# core.net
KiCad netlist of a schematic drawn in EAGLE
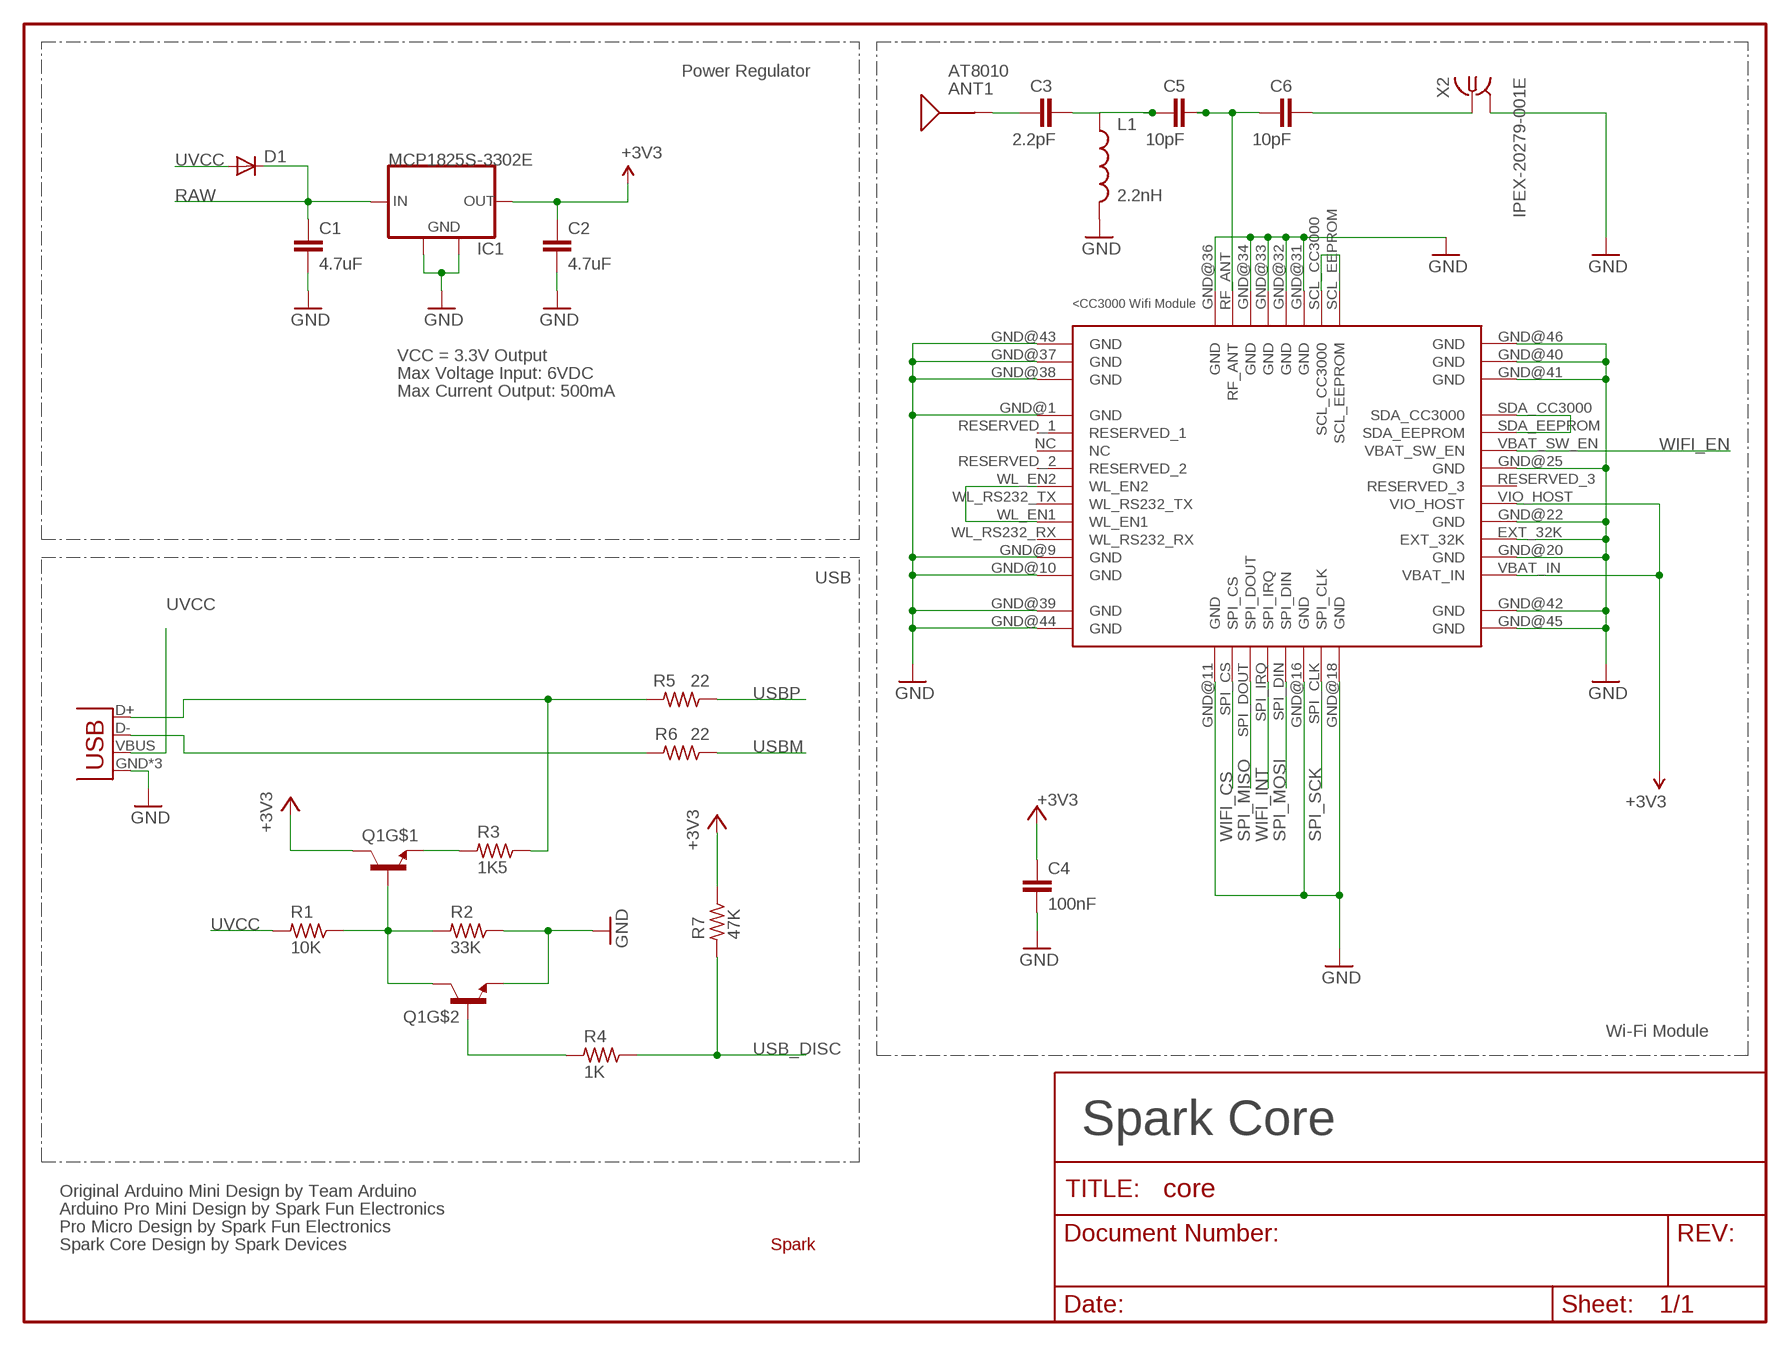
[diagram p0: schematic, sheet 1, part 1 of 2]
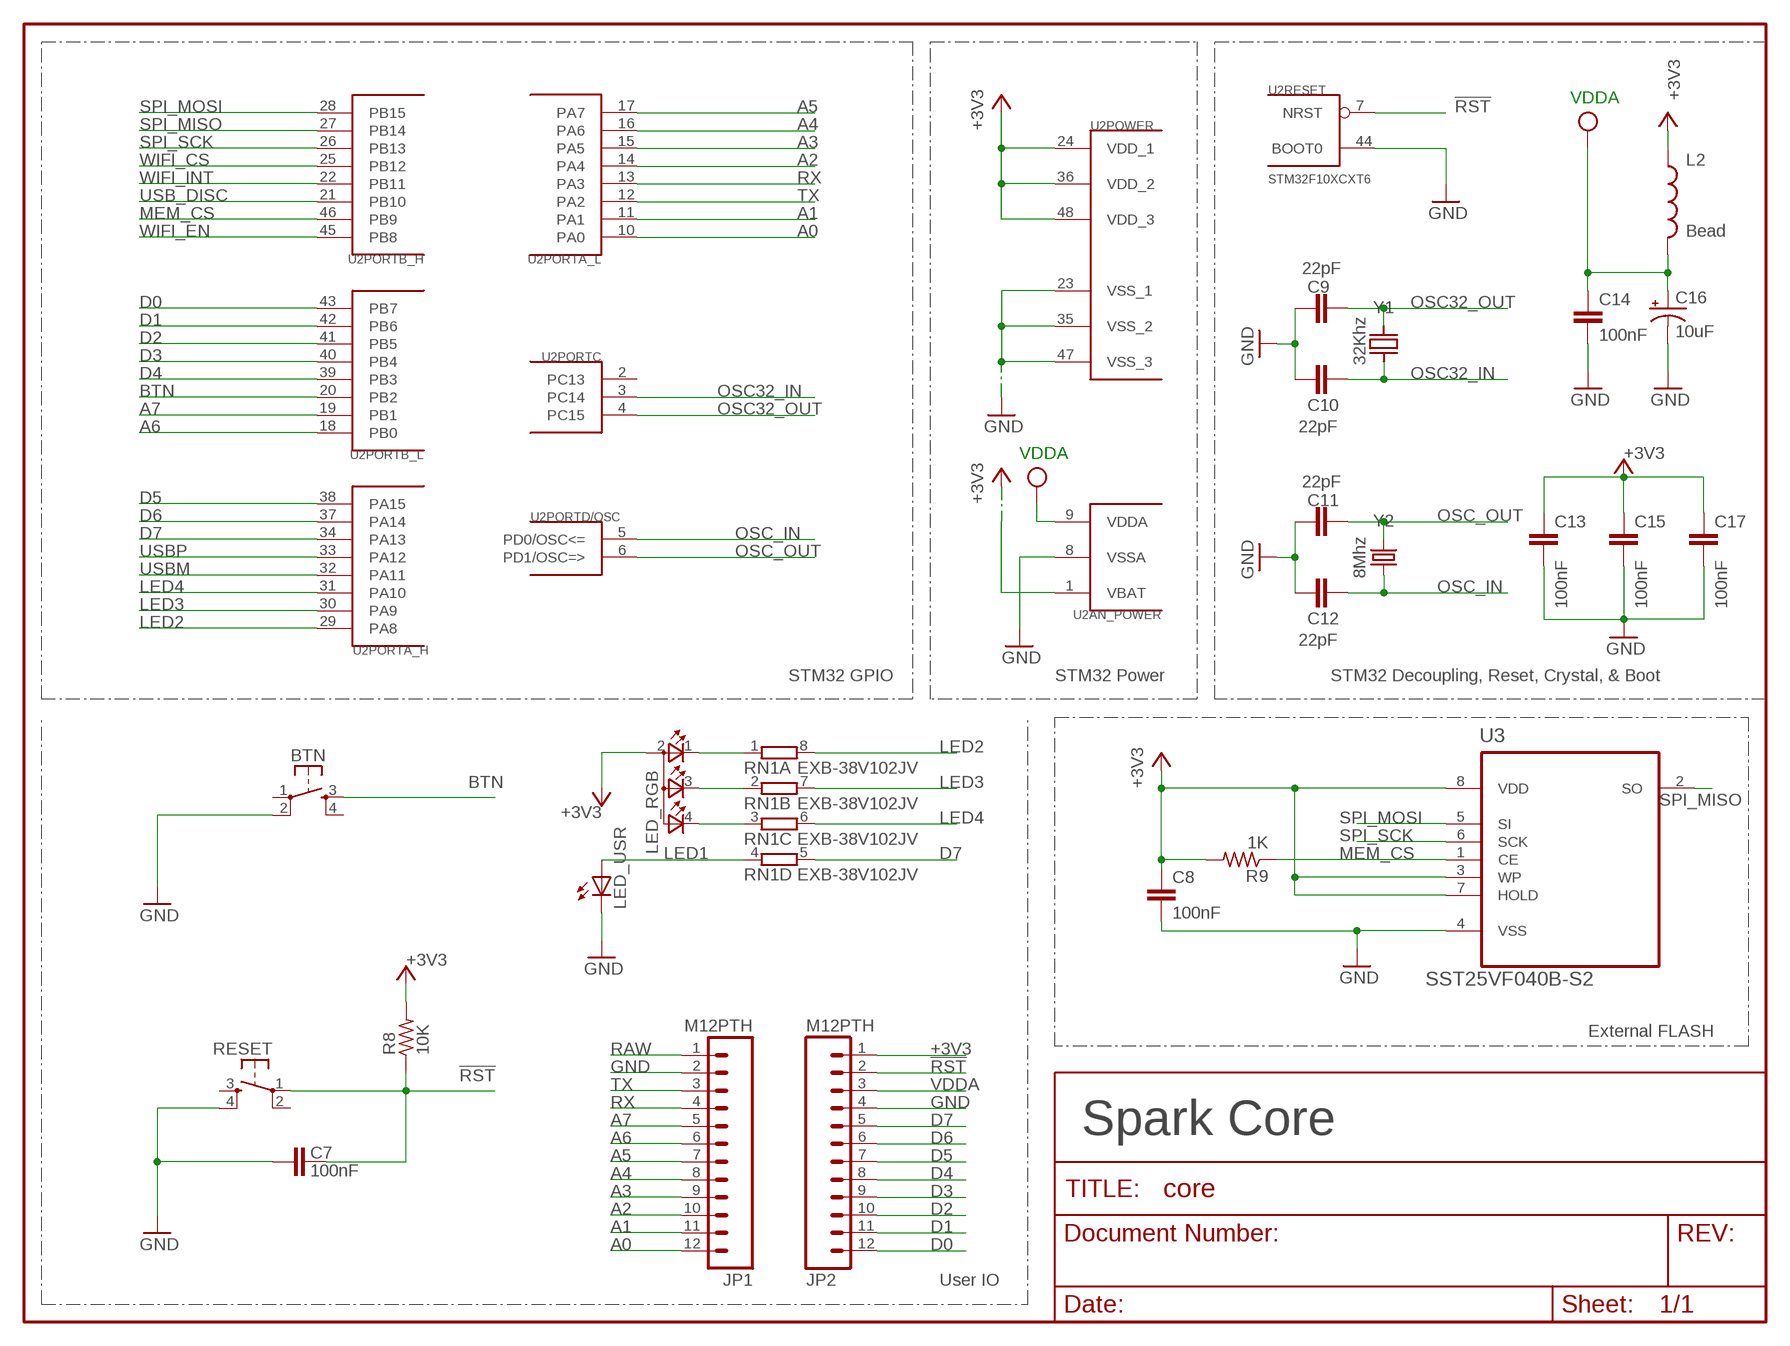
[diagram p1: schematic, sheet 1, part 2 of 2]

(export (version "E")
  (design (tool "Eeschema 10.0.6"))
  (components
    (comp (ref "ANT1")
      (value "AT8010")
      (footprint "eagle-import:AT8010")
      (libsource (lib "eagle-import") (part "AT8010"))
    )
    (comp (ref "BTN")
      (value "KMR211GLFS")
      (footprint "eagle-import:TACTILE_SWITCH_SMD")
      (libsource (lib "eagle-import") (part "TAC_SWITCHSMD"))
    )
    (comp (ref "C1")
      (value "4.7uF")
      (footprint "eagle-import:C0603")
      (libsource (lib "eagle-import") (part "C-EUC0603"))
    )
    (comp (ref "C2")
      (value "4.7uF")
      (footprint "eagle-import:C0603")
      (libsource (lib "eagle-import") (part "C-EUC0603"))
    )
    (comp (ref "C3")
      (value "2.2pF")
      (footprint "eagle-import:C0603")
      (libsource (lib "eagle-import") (part "C-EUC0603"))
    )
    (comp (ref "C4")
      (value "100nF")
      (footprint "eagle-import:C0603")
      (libsource (lib "eagle-import") (part "C-EUC0603"))
    )
    (comp (ref "C5")
      (value "10pF")
      (footprint "eagle-import:C0603")
      (libsource (lib "eagle-import") (part "C-EUC0603"))
    )
    (comp (ref "C6")
      (value "10pF")
      (footprint "eagle-import:C0603")
      (libsource (lib "eagle-import") (part "C-EUC0603"))
    )
    (comp (ref "C7")
      (value "100nF")
      (footprint "eagle-import:C0603")
      (libsource (lib "eagle-import") (part "C-EUC0603"))
    )
    (comp (ref "C8")
      (value "100nF")
      (footprint "eagle-import:C0603")
      (libsource (lib "eagle-import") (part "C-EUC0603"))
    )
    (comp (ref "C9")
      (value "22pF")
      (footprint "eagle-import:C0603")
      (libsource (lib "eagle-import") (part "C-EUC0603"))
    )
    (comp (ref "C10")
      (value "22pF")
      (footprint "eagle-import:C0603")
      (libsource (lib "eagle-import") (part "C-EUC0603"))
    )
    (comp (ref "C11")
      (value "22pF")
      (footprint "eagle-import:C0603")
      (libsource (lib "eagle-import") (part "C-EUC0603"))
    )
    (comp (ref "C12")
      (value "22pF")
      (footprint "eagle-import:C0603")
      (libsource (lib "eagle-import") (part "C-EUC0603"))
    )
    (comp (ref "C13")
      (value "100nF")
      (footprint "eagle-import:C0603")
      (libsource (lib "eagle-import") (part "C-EUC0603"))
    )
    (comp (ref "C14")
      (value "100nF")
      (footprint "eagle-import:C0603")
      (libsource (lib "eagle-import") (part "C-EUC0603"))
    )
    (comp (ref "C15")
      (value "100nF")
      (footprint "eagle-import:C0603")
      (libsource (lib "eagle-import") (part "C-EUC0603"))
    )
    (comp (ref "C16")
      (value "10uF")
      (footprint "eagle-import:EIA3216")
      (libsource (lib "eagle-import") (part "TANT-CAP1206"))
    )
    (comp (ref "C17")
      (value "100nF")
      (footprint "eagle-import:C0603")
      (libsource (lib "eagle-import") (part "C-EUC0603"))
    )
    (comp (ref "D1")
      (value "DIODESOD")
      (footprint "eagle-import:SOD-323")
      (libsource (lib "eagle-import") (part "DIODESOD"))
    )
    (comp (ref "IC1")
      (value "MCP1825S-3302E")
      (footprint "eagle-import:SOT223")
      (libsource (lib "eagle-import") (part "MCP1825S-SOT223"))
    )
    (comp (ref "JP1")
      (value "M12PTH")
      (footprint "eagle-import:1X12-SMALL-PADS")
      (libsource (lib "eagle-import") (part "M12PTH"))
    )
    (comp (ref "JP2")
      (value "M12PTH")
      (footprint "eagle-import:1X12-SMALL-PADS")
      (libsource (lib "eagle-import") (part "M12PTH"))
    )
    (comp (ref "L1")
      (value "2.2nH")
      (footprint "eagle-import:0603")
      (libsource (lib "eagle-import") (part "INDUCTOR0603"))
    )
    (comp (ref "L2")
      (value "Bead")
      (footprint "eagle-import:0603")
      (libsource (lib "eagle-import") (part "INDUCTOR0603"))
    )
    (comp (ref "LED_RGB")
      (value "TOPLED-3PLCC")
      (footprint "eagle-import:P-LCC-4-3")
      (libsource (lib "eagle-import") (part "TOPLED-3PLCC"))
    )
    (comp (ref "LED_USR")
      (value "LED0603")
      (footprint "eagle-import:LED-0603")
      (libsource (lib "eagle-import") (part "LED0603"))
    )
    (comp (ref "Q1")
      (value "MMDT3904")
      (footprint "eagle-import:SOT363")
      (libsource (lib "eagle-import") (part "MMDT3904"))
    )
    (comp (ref "R1")
      (value "10K")
      (footprint "eagle-import:R0603")
      (libsource (lib "eagle-import") (part "R-US_R0603"))
    )
    (comp (ref "R2")
      (value "33K")
      (footprint "eagle-import:R0603")
      (libsource (lib "eagle-import") (part "R-US_R0603"))
    )
    (comp (ref "R3")
      (value "1K5")
      (footprint "eagle-import:R0603")
      (libsource (lib "eagle-import") (part "R-US_R0603"))
    )
    (comp (ref "R4")
      (value "1K")
      (footprint "eagle-import:R0603")
      (libsource (lib "eagle-import") (part "R-US_R0603"))
    )
    (comp (ref "R5")
      (value "22")
      (footprint "eagle-import:R0603")
      (libsource (lib "eagle-import") (part "R-US_R0603"))
    )
    (comp (ref "R6")
      (value "22")
      (footprint "eagle-import:R0603")
      (libsource (lib "eagle-import") (part "R-US_R0603"))
    )
    (comp (ref "R7")
      (value "47K")
      (footprint "eagle-import:R0603")
      (libsource (lib "eagle-import") (part "R-US_R0603"))
    )
    (comp (ref "R8")
      (value "10K")
      (footprint "eagle-import:R0603")
      (libsource (lib "eagle-import") (part "R-US_R0603"))
    )
    (comp (ref "R9")
      (value "1K")
      (footprint "eagle-import:R0603")
      (libsource (lib "eagle-import") (part "R-US_R0603"))
    )
    (comp (ref "RESET")
      (value "KMR211GLFS")
      (footprint "eagle-import:TACTILE_SWITCH_SMD")
      (libsource (lib "eagle-import") (part "TAC_SWITCHSMD"))
    )
    (comp (ref "RN1")
      (value "EXB-38V102JV")
      (footprint "eagle-import:EXB38V")
      (libsource (lib "eagle-import") (part "4R-NEXB38V"))
    )
    (comp (ref "U$1")
      (value "SPARK_LOGO2")
      (footprint "eagle-import:SPARK_LOGO2")
      (libsource (lib "eagle-import") (part "SPARK_LOGO2"))
    )
    (comp (ref "U1")
      (value "CC3000")
      (footprint "eagle-import:CC3000")
      (libsource (lib "eagle-import") (part "CC3000"))
    )
    (comp (ref "U2")
      (value "STM32F10XCXT6")
      (footprint "eagle-import:TQFP48")
      (libsource (lib "eagle-import") (part "STM32F10XCXT6"))
    )
    (comp (ref "U3")
      (value "SST25VF040B-S2")
      (footprint "eagle-import:SOIC127P790X216-8N")
      (libsource (lib "eagle-import") (part "SST25VF040B-S2"))
    )
    (comp (ref "X1")
      (value "USB-MICROB")
      (footprint "eagle-import:USB-MICROB-SLOT-HOLE")
      (libsource (lib "eagle-import") (part "USBUSB-MICROB-SLOT-HOLE"))
    )
    (comp (ref "X2")
      (value "IPEX-20279-001E")
      (footprint "eagle-import:IPEX-20279-001E")
      (libsource (lib "eagle-import") (part "IPEX-20279-001E"))
    )
    (comp (ref "Y1")
      (value "32Khz")
      (footprint "eagle-import:FC135")
      (libsource (lib "eagle-import") (part "Q_FC135"))
    )
    (comp (ref "Y2")
      (value "8Mhz")
      (footprint "eagle-import:CRYSTAL-SMD-5X3")
      (libsource (lib "eagle-import") (part "CRYSTAL5X3"))
    )
  )
  (nets
    (net (code "1") (name "+3V3") (class "Default")
      (node (ref "C13") (pin "1") (pinfunction "1_1") (pintype "passive"))
      (node (ref "C15") (pin "1") (pinfunction "1_1") (pintype "passive"))
      (node (ref "C17") (pin "1") (pinfunction "1_1") (pintype "passive"))
      (node (ref "C2") (pin "1") (pinfunction "1_1") (pintype "passive"))
      (node (ref "C4") (pin "1") (pinfunction "1_1") (pintype "passive"))
      (node (ref "C8") (pin "1") (pinfunction "1_1") (pintype "passive"))
      (node (ref "IC1") (pin "3") (pinfunction "OUT_3") (pintype "output"))
      (node (ref "JP2") (pin "1") (pinfunction "1_1") (pintype "passive"))
      (node (ref "L2") (pin "1") (pinfunction "1_1") (pintype "passive"))
      (node (ref "LED_RGB") (pin "2") (pinfunction "A2_2") (pintype "passive"))
      (node (ref "Q1") (pin "3") (pinfunction "C_3") (pintype "passive"))
      (node (ref "R7") (pin "1") (pinfunction "1_1") (pintype "passive"))
      (node (ref "R8") (pin "2") (pinfunction "2_2") (pintype "passive"))
      (node (ref "R9") (pin "2") (pinfunction "2_2") (pintype "passive"))
      (node (ref "U1") (pin "VBAT_IN") (pinfunction "VBAT_IN_VBAT_IN") (pintype "power_in"))
      (node (ref "U1") (pin "VIO_HOST") (pinfunction "VIO_HOST_VIO_HOST") (pintype "power_in"))
      (node (ref "U2") (pin "1") (pinfunction "VBAT_1") (pintype "power_in"))
      (node (ref "U2") (pin "24") (pinfunction "VDD_1_24") (pintype "power_in"))
      (node (ref "U2") (pin "36") (pinfunction "VDD_2_36") (pintype "power_in"))
      (node (ref "U2") (pin "48") (pinfunction "VDD_3_48") (pintype "power_in"))
      (node (ref "U3") (pin "3") (pinfunction "WP_3") (pintype "input"))
      (node (ref "U3") (pin "7") (pinfunction "HOLD_7") (pintype "input"))
      (node (ref "U3") (pin "8") (pinfunction "VDD_8") (pintype "power_in"))
    )
    (net (code "2") (name "/A0") (class "Default")
      (node (ref "JP1") (pin "12") (pinfunction "12_12") (pintype "passive"))
      (node (ref "U2") (pin "10") (pinfunction "PA0_10") (pintype "bidirectional"))
    )
    (net (code "3") (name "/A1") (class "Default")
      (node (ref "JP1") (pin "11") (pinfunction "11_11") (pintype "passive"))
      (node (ref "U2") (pin "11") (pinfunction "PA1_11") (pintype "bidirectional"))
    )
    (net (code "4") (name "/A2") (class "Default")
      (node (ref "JP1") (pin "10") (pinfunction "10_10") (pintype "passive"))
      (node (ref "U2") (pin "14") (pinfunction "PA4_14") (pintype "bidirectional"))
    )
    (net (code "5") (name "/A3") (class "Default")
      (node (ref "JP1") (pin "9") (pinfunction "9_9") (pintype "passive"))
      (node (ref "U2") (pin "15") (pinfunction "PA5_15") (pintype "bidirectional"))
    )
    (net (code "6") (name "/A4") (class "Default")
      (node (ref "JP1") (pin "8") (pinfunction "8_8") (pintype "passive"))
      (node (ref "U2") (pin "16") (pinfunction "PA6_16") (pintype "bidirectional"))
    )
    (net (code "7") (name "/A5") (class "Default")
      (node (ref "JP1") (pin "7") (pinfunction "7_7") (pintype "passive"))
      (node (ref "U2") (pin "17") (pinfunction "PA7_17") (pintype "bidirectional"))
    )
    (net (code "8") (name "/A6") (class "Default")
      (node (ref "JP1") (pin "6") (pinfunction "6_6") (pintype "passive"))
      (node (ref "U2") (pin "18") (pinfunction "PB0_18") (pintype "bidirectional"))
    )
    (net (code "9") (name "/A7") (class "Default")
      (node (ref "JP1") (pin "5") (pinfunction "5_5") (pintype "passive"))
      (node (ref "U2") (pin "19") (pinfunction "PB1_19") (pintype "bidirectional"))
    )
    (net (code "10") (name "/BTN") (class "Default")
      (node (ref "BTN") (pin "3") (pinfunction "3_3") (pintype "passive"))
      (node (ref "U2") (pin "20") (pinfunction "PB2_20") (pintype "bidirectional"))
    )
    (net (code "11") (name "/D0") (class "Default")
      (node (ref "JP2") (pin "12") (pinfunction "12_12") (pintype "passive"))
      (node (ref "U2") (pin "43") (pinfunction "PB7_43") (pintype "bidirectional"))
    )
    (net (code "12") (name "/D1") (class "Default")
      (node (ref "JP2") (pin "11") (pinfunction "11_11") (pintype "passive"))
      (node (ref "U2") (pin "42") (pinfunction "PB6_42") (pintype "bidirectional"))
    )
    (net (code "13") (name "/D2") (class "Default")
      (node (ref "JP2") (pin "10") (pinfunction "10_10") (pintype "passive"))
      (node (ref "U2") (pin "41") (pinfunction "PB5_41") (pintype "bidirectional"))
    )
    (net (code "14") (name "/D3") (class "Default")
      (node (ref "JP2") (pin "9") (pinfunction "9_9") (pintype "passive"))
      (node (ref "U2") (pin "40") (pinfunction "PB4_40") (pintype "bidirectional"))
    )
    (net (code "15") (name "/D4") (class "Default")
      (node (ref "JP2") (pin "8") (pinfunction "8_8") (pintype "passive"))
      (node (ref "U2") (pin "39") (pinfunction "PB3_39") (pintype "bidirectional"))
    )
    (net (code "16") (name "/D5") (class "Default")
      (node (ref "JP2") (pin "7") (pinfunction "7_7") (pintype "passive"))
      (node (ref "U2") (pin "38") (pinfunction "PA15_38") (pintype "bidirectional"))
    )
    (net (code "17") (name "/D6") (class "Default")
      (node (ref "JP2") (pin "6") (pinfunction "6_6") (pintype "passive"))
      (node (ref "U2") (pin "37") (pinfunction "PA14_37") (pintype "bidirectional"))
    )
    (net (code "18") (name "/D7") (class "Default")
      (node (ref "JP2") (pin "5") (pinfunction "5_5") (pintype "passive"))
      (node (ref "RN1") (pin "5") (pinfunction "2_5") (pintype "passive"))
      (node (ref "U2") (pin "34") (pinfunction "PA13_34") (pintype "bidirectional"))
    )
    (net (code "19") (name "/LED1") (class "Default")
      (node (ref "LED_USR") (pin "A") (pinfunction "A_A") (pintype "passive"))
      (node (ref "RN1") (pin "4") (pinfunction "1_4") (pintype "passive"))
    )
    (net (code "20") (name "/LED2") (class "Default")
      (node (ref "RN1") (pin "8") (pinfunction "2_8") (pintype "passive"))
      (node (ref "U2") (pin "29") (pinfunction "PA8_29") (pintype "bidirectional"))
    )
    (net (code "21") (name "/LED3") (class "Default")
      (node (ref "RN1") (pin "7") (pinfunction "2_7") (pintype "passive"))
      (node (ref "U2") (pin "30") (pinfunction "PA9_30") (pintype "bidirectional"))
    )
    (net (code "22") (name "/LED4") (class "Default")
      (node (ref "RN1") (pin "6") (pinfunction "2_6") (pintype "passive"))
      (node (ref "U2") (pin "31") (pinfunction "PA10_31") (pintype "bidirectional"))
    )
    (net (code "23") (name "/MEM_CS") (class "Default")
      (node (ref "R9") (pin "1") (pinfunction "1_1") (pintype "passive"))
      (node (ref "U2") (pin "46") (pinfunction "PB9_46") (pintype "bidirectional"))
      (node (ref "U3") (pin "1") (pinfunction "CE_1") (pintype "input"))
    )
    (net (code "24") (name "/OSC32_IN") (class "Default")
      (node (ref "C10") (pin "1") (pinfunction "1_1") (pintype "passive"))
      (node (ref "U2") (pin "3") (pinfunction "PC14_3") (pintype "bidirectional"))
      (node (ref "Y1") (pin "X1") (pinfunction "1_X1") (pintype "passive"))
    )
    (net (code "25") (name "/OSC32_OUT") (class "Default")
      (node (ref "C9") (pin "1") (pinfunction "1_1") (pintype "passive"))
      (node (ref "U2") (pin "4") (pinfunction "PC15_4") (pintype "bidirectional"))
      (node (ref "Y1") (pin "X2") (pinfunction "2_X2") (pintype "passive"))
    )
    (net (code "26") (name "/OSC_IN") (class "Default")
      (node (ref "C12") (pin "1") (pinfunction "1_1") (pintype "passive"))
      (node (ref "U2") (pin "5") (pinfunction "PD0/OSC<=_5") (pintype "bidirectional"))
      (node (ref "Y2") (pin "1") (pinfunction "1_1") (pintype "passive"))
    )
    (net (code "27") (name "/OSC_OUT") (class "Default")
      (node (ref "C11") (pin "1") (pinfunction "1_1") (pintype "passive"))
      (node (ref "U2") (pin "6") (pinfunction "PD1/OSC=>_6") (pintype "bidirectional"))
      (node (ref "Y2") (pin "3") (pinfunction "2_3") (pintype "passive"))
    )
    (net (code "28") (name "/RAW") (class "Default")
      (node (ref "C1") (pin "1") (pinfunction "1_1") (pintype "passive"))
      (node (ref "D1") (pin "1") (pinfunction "C_1") (pintype "passive"))
      (node (ref "IC1") (pin "1") (pinfunction "IN_1") (pintype "input"))
      (node (ref "JP1") (pin "1") (pinfunction "1_1") (pintype "passive"))
    )
    (net (code "29") (name "/RX") (class "Default")
      (node (ref "JP1") (pin "4") (pinfunction "4_4") (pintype "passive"))
      (node (ref "U2") (pin "13") (pinfunction "PA3_13") (pintype "bidirectional"))
    )
    (net (code "30") (name "/SPI_MISO") (class "Default")
      (node (ref "U1") (pin "SPI_DOUT") (pinfunction "SPI_DOUT_SPI_DOUT") (pintype "output"))
      (node (ref "U2") (pin "27") (pinfunction "PB14_27") (pintype "bidirectional"))
      (node (ref "U3") (pin "2") (pinfunction "SO_2") (pintype "output"))
    )
    (net (code "31") (name "/SPI_MOSI") (class "Default")
      (node (ref "U1") (pin "SPI_DIN") (pinfunction "SPI_DIN_SPI_DIN") (pintype "input"))
      (node (ref "U2") (pin "28") (pinfunction "PB15_28") (pintype "bidirectional"))
      (node (ref "U3") (pin "5") (pinfunction "SI_5") (pintype "input"))
    )
    (net (code "32") (name "/SPI_SCK") (class "Default")
      (node (ref "U1") (pin "SPI_CLK") (pinfunction "SPI_CLK_SPI_CLK") (pintype "input"))
      (node (ref "U2") (pin "26") (pinfunction "PB13_26") (pintype "bidirectional"))
      (node (ref "U3") (pin "6") (pinfunction "SCK_6") (pintype "input"))
    )
    (net (code "33") (name "/TX") (class "Default")
      (node (ref "JP1") (pin "3") (pinfunction "3_3") (pintype "passive"))
      (node (ref "U2") (pin "12") (pinfunction "PA2_12") (pintype "bidirectional"))
    )
    (net (code "34") (name "/USBM") (class "Default")
      (node (ref "R6") (pin "1") (pinfunction "1_1") (pintype "passive"))
      (node (ref "U2") (pin "32") (pinfunction "PA11_32") (pintype "bidirectional"))
    )
    (net (code "35") (name "/USBP") (class "Default")
      (node (ref "R5") (pin "1") (pinfunction "1_1") (pintype "passive"))
      (node (ref "U2") (pin "33") (pinfunction "PA12_33") (pintype "bidirectional"))
    )
    (net (code "36") (name "/USB_DISC") (class "Default")
      (node (ref "R4") (pin "1") (pinfunction "1_1") (pintype "passive"))
      (node (ref "R7") (pin "2") (pinfunction "2_2") (pintype "passive"))
      (node (ref "U2") (pin "21") (pinfunction "PB10_21") (pintype "bidirectional"))
    )
    (net (code "37") (name "/UVCC") (class "Default")
      (node (ref "D1") (pin "2") (pinfunction "A_2") (pintype "passive"))
      (node (ref "R1") (pin "2") (pinfunction "2_2") (pintype "passive"))
      (node (ref "X1") (pin "VBUS") (pinfunction "VBUS_VBUS") (pintype "bidirectional"))
    )
    (net (code "38") (name "/WIFI_CS") (class "Default")
      (node (ref "U1") (pin "SPI_CS") (pinfunction "SPI_CS_SPI_CS") (pintype "input"))
      (node (ref "U2") (pin "25") (pinfunction "PB12_25") (pintype "bidirectional"))
    )
    (net (code "39") (name "/WIFI_EN") (class "Default")
      (node (ref "U1") (pin "VBAT_SW_EN") (pinfunction "VBAT_SW_EN_VBAT_SW_EN") (pintype "input"))
      (node (ref "U2") (pin "45") (pinfunction "PB8_45") (pintype "bidirectional"))
    )
    (net (code "40") (name "/WIFI_INT") (class "Default")
      (node (ref "U1") (pin "SPI_IRQ") (pinfunction "SPI_IRQ_SPI_IRQ") (pintype "output"))
      (node (ref "U2") (pin "22") (pinfunction "PB11_22") (pintype "bidirectional"))
    )
    (net (code "41") (name "/~{RST}") (class "Default")
      (node (ref "C7") (pin "2") (pinfunction "2_2") (pintype "passive"))
      (node (ref "JP2") (pin "2") (pinfunction "2_2") (pintype "passive"))
      (node (ref "R8") (pin "1") (pinfunction "1_1") (pintype "passive"))
      (node (ref "RESET") (pin "1") (pinfunction "1_1") (pintype "passive"))
      (node (ref "U2") (pin "7") (pinfunction "NRST_7") (pintype "input"))
    )
    (net (code "42") (name "GND") (class "Default")
      (node (ref "BTN") (pin "2") (pinfunction "2_2") (pintype "passive"))
      (node (ref "C1") (pin "2") (pinfunction "2_2") (pintype "passive"))
      (node (ref "C10") (pin "2") (pinfunction "2_2") (pintype "passive"))
      (node (ref "C11") (pin "2") (pinfunction "2_2") (pintype "passive"))
      (node (ref "C12") (pin "2") (pinfunction "2_2") (pintype "passive"))
      (node (ref "C13") (pin "2") (pinfunction "2_2") (pintype "passive"))
      (node (ref "C14") (pin "2") (pinfunction "2_2") (pintype "passive"))
      (node (ref "C15") (pin "2") (pinfunction "2_2") (pintype "passive"))
      (node (ref "C16") (pin "C") (pinfunction "-_C") (pintype "passive"))
      (node (ref "C17") (pin "2") (pinfunction "2_2") (pintype "passive"))
      (node (ref "C2") (pin "2") (pinfunction "2_2") (pintype "passive"))
      (node (ref "C4") (pin "2") (pinfunction "2_2") (pintype "passive"))
      (node (ref "C7") (pin "1") (pinfunction "1_1") (pintype "passive"))
      (node (ref "C8") (pin "2") (pinfunction "2_2") (pintype "passive"))
      (node (ref "C9") (pin "2") (pinfunction "2_2") (pintype "passive"))
      (node (ref "IC1") (pin "2") (pinfunction "GND_2") (pintype "power_in"))
      (node (ref "IC1") (pin "4") (pinfunction "GND_4") (pintype "power_in"))
      (node (ref "JP1") (pin "2") (pinfunction "2_2") (pintype "passive"))
      (node (ref "JP2") (pin "4") (pinfunction "4_4") (pintype "passive"))
      (node (ref "L1") (pin "2") (pinfunction "2_2") (pintype "passive"))
      (node (ref "LED_USR") (pin "C") (pinfunction "C_C") (pintype "passive"))
      (node (ref "Q1") (pin "1") (pinfunction "E_1") (pintype "passive"))
      (node (ref "R2") (pin "1") (pinfunction "1_1") (pintype "passive"))
      (node (ref "RESET") (pin "4") (pinfunction "4_4") (pintype "passive"))
      (node (ref "U1") (pin "EXT_32K") (pinfunction "EXT_32K_EXT_32K") (pintype "bidirectional"))
      (node (ref "U1") (pin "GND@1") (pinfunction "GND_GND@1") (pintype "power_in"))
      (node (ref "U1") (pin "GND@10") (pinfunction "GND_GND@10") (pintype "power_in"))
      (node (ref "U1") (pin "GND@11") (pinfunction "GND_GND@11") (pintype "power_in"))
      (node (ref "U1") (pin "GND@16") (pinfunction "GND_GND@16") (pintype "power_in"))
      (node (ref "U1") (pin "GND@18") (pinfunction "GND_GND@18") (pintype "power_in"))
      (node (ref "U1") (pin "GND@20") (pinfunction "GND_GND@20") (pintype "power_in"))
      (node (ref "U1") (pin "GND@22") (pinfunction "GND_GND@22") (pintype "power_in"))
      (node (ref "U1") (pin "GND@25") (pinfunction "GND_GND@25") (pintype "power_in"))
      (node (ref "U1") (pin "GND@31") (pinfunction "GND_GND@31") (pintype "power_in"))
      (node (ref "U1") (pin "GND@32") (pinfunction "GND_GND@32") (pintype "power_in"))
      (node (ref "U1") (pin "GND@33") (pinfunction "GND_GND@33") (pintype "power_in"))
      (node (ref "U1") (pin "GND@34") (pinfunction "GND_GND@34") (pintype "power_in"))
      (node (ref "U1") (pin "GND@36") (pinfunction "GND_GND@36") (pintype "power_in"))
      (node (ref "U1") (pin "GND@37") (pinfunction "GND_GND@37") (pintype "power_in"))
      (node (ref "U1") (pin "GND@38") (pinfunction "GND_GND@38") (pintype "power_in"))
      (node (ref "U1") (pin "GND@39") (pinfunction "GND_GND@39") (pintype "power_in"))
      (node (ref "U1") (pin "GND@40") (pinfunction "GND_GND@40") (pintype "power_in"))
      (node (ref "U1") (pin "GND@41") (pinfunction "GND_GND@41") (pintype "power_in"))
      (node (ref "U1") (pin "GND@42") (pinfunction "GND_GND@42") (pintype "power_in"))
      (node (ref "U1") (pin "GND@43") (pinfunction "GND_GND@43") (pintype "power_in"))
      (node (ref "U1") (pin "GND@44") (pinfunction "GND_GND@44") (pintype "power_in"))
      (node (ref "U1") (pin "GND@45") (pinfunction "GND_GND@45") (pintype "power_in"))
      (node (ref "U1") (pin "GND@46") (pinfunction "GND_GND@46") (pintype "power_in"))
      (node (ref "U1") (pin "GND@9") (pinfunction "GND_GND@9") (pintype "power_in"))
      (node (ref "U2") (pin "23") (pinfunction "VSS_1_23") (pintype "power_in"))
      (node (ref "U2") (pin "35") (pinfunction "VSS_2_35") (pintype "power_in"))
      (node (ref "U2") (pin "44") (pinfunction "BOOT0_44") (pintype "input"))
      (node (ref "U2") (pin "47") (pinfunction "VSS_3_47") (pintype "power_in"))
      (node (ref "U2") (pin "8") (pinfunction "VSSA_8") (pintype "power_in"))
      (node (ref "U3") (pin "4") (pinfunction "VSS_4") (pintype "passive"))
      (node (ref "X1") (pin "GND") (pinfunction "GND_GND") (pintype "bidirectional"))
      (node (ref "X1") (pin "MT1") (pinfunction "GND_MT1") (pintype "bidirectional"))
      (node (ref "X1") (pin "MT2") (pinfunction "GND_MT2") (pintype "bidirectional"))
      (node (ref "X2") (pin "2@1") (pinfunction "GND_2@1") (pintype "passive"))
      (node (ref "X2") (pin "2@2") (pinfunction "GND_2@2") (pintype "passive"))
    )
    (net (code "43") (name "Net-(ANT1-SIGNAL)") (class "Default")
      (node (ref "ANT1") (pin "SIG") (pinfunction "SIGNAL_SIG") (pintype "bidirectional"))
      (node (ref "C3") (pin "1") (pinfunction "1_1") (pintype "passive"))
    )
    (net (code "44") (name "Net-(C3-Pad2)") (class "Default")
      (node (ref "C3") (pin "2") (pinfunction "2_2") (pintype "passive"))
      (node (ref "C5") (pin "1") (pinfunction "1_1") (pintype "passive"))
      (node (ref "L1") (pin "1") (pinfunction "1_1") (pintype "passive"))
    )
    (net (code "45") (name "Net-(C5-Pad2)") (class "Default")
      (node (ref "C5") (pin "2") (pinfunction "2_2") (pintype "passive"))
      (node (ref "C6") (pin "1") (pinfunction "1_1") (pintype "passive"))
      (node (ref "U1") (pin "RF_ANT") (pinfunction "RF_ANT_RF_ANT") (pintype "bidirectional"))
    )
    (net (code "46") (name "Net-(C6-Pad2)") (class "Default")
      (node (ref "C6") (pin "2") (pinfunction "2_2") (pintype "passive"))
      (node (ref "X2") (pin "1") (pinfunction "1_1") (pintype "passive"))
    )
    (net (code "47") (name "Net-(LED_RGB-CBLUE)") (class "Default")
      (node (ref "LED_RGB") (pin "3") (pinfunction "CBLUE_3") (pintype "passive"))
      (node (ref "RN1") (pin "2") (pinfunction "1_2") (pintype "passive"))
    )
    (net (code "48") (name "Net-(LED_RGB-CGREEN)") (class "Default")
      (node (ref "LED_RGB") (pin "4") (pinfunction "CGREEN_4") (pintype "passive"))
      (node (ref "RN1") (pin "3") (pinfunction "1_3") (pintype "passive"))
    )
    (net (code "49") (name "Net-(LED_RGB-CRED)") (class "Default")
      (node (ref "LED_RGB") (pin "1") (pinfunction "CRED_1") (pintype "passive"))
      (node (ref "RN1") (pin "1") (pinfunction "1_1") (pintype "passive"))
    )
    (net (code "50") (name "Net-(Q1A-B)") (class "Default")
      (node (ref "Q1") (pin "5") (pinfunction "B_5") (pintype "passive"))
      (node (ref "Q1") (pin "6") (pinfunction "C_6") (pintype "passive"))
      (node (ref "R1") (pin "1") (pinfunction "1_1") (pintype "passive"))
      (node (ref "R2") (pin "2") (pinfunction "2_2") (pintype "passive"))
    )
    (net (code "51") (name "Net-(Q1A-E)") (class "Default")
      (node (ref "Q1") (pin "4") (pinfunction "E_4") (pintype "passive"))
      (node (ref "R3") (pin "2") (pinfunction "2_2") (pintype "passive"))
    )
    (net (code "52") (name "Net-(Q1B-B)") (class "Default")
      (node (ref "Q1") (pin "2") (pinfunction "B_2") (pintype "passive"))
      (node (ref "R4") (pin "2") (pinfunction "2_2") (pintype "passive"))
    )
    (net (code "53") (name "Net-(R3-Pad1)") (class "Default")
      (node (ref "R3") (pin "1") (pinfunction "1_1") (pintype "passive"))
      (node (ref "R5") (pin "2") (pinfunction "2_2") (pintype "passive"))
      (node (ref "X1") (pin "D+") (pinfunction "D+_D+") (pintype "bidirectional"))
    )
    (net (code "54") (name "Net-(R6-Pad2)") (class "Default")
      (node (ref "R6") (pin "2") (pinfunction "2_2") (pintype "passive"))
      (node (ref "X1") (pin "D-") (pinfunction "D-_D-") (pintype "bidirectional"))
    )
    (net (code "55") (name "Net-(U1-PadSCL_CC3000)") (class "Default")
      (node (ref "U1") (pin "SCL_CC3000") (pinfunction "SCL_CC3000_SCL_CC3000") (pintype "bidirectional"))
      (node (ref "U1") (pin "SCL_EEPROM") (pinfunction "SCL_EEPROM_SCL_EEPROM") (pintype "bidirectional"))
    )
    (net (code "56") (name "Net-(U1-PadSDA_CC3000)") (class "Default")
      (node (ref "U1") (pin "SDA_CC3000") (pinfunction "SDA_CC3000_SDA_CC3000") (pintype "bidirectional"))
      (node (ref "U1") (pin "SDA_EEPROM") (pinfunction "SDA_EEPROM_SDA_EEPROM") (pintype "bidirectional"))
    )
    (net (code "57") (name "Net-(U1-PadWL_EN1)") (class "Default")
      (node (ref "U1") (pin "WL_EN1") (pinfunction "WL_EN1_WL_EN1") (pintype "input"))
      (node (ref "U1") (pin "WL_EN2") (pinfunction "WL_EN2_WL_EN2") (pintype "input"))
    )
    (net (code "58") (name "VCC") (class "Default")
      (node (ref "C14") (pin "1") (pinfunction "1_1") (pintype "passive"))
      (node (ref "C16") (pin "A") (pinfunction "+_A") (pintype "passive"))
      (node (ref "JP2") (pin "3") (pinfunction "3_3") (pintype "passive"))
      (node (ref "L2") (pin "2") (pinfunction "2_2") (pintype "passive"))
      (node (ref "U2") (pin "9") (pinfunction "VDDA_9") (pintype "power_in"))
    )
    (net (code "59") (name "unconnected-(BTN-Pad1)") (class "Default")
      (node (ref "BTN") (pin "1") (pinfunction "1_1") (pintype "passive"))
    )
    (net (code "60") (name "unconnected-(BTN-Pad4)") (class "Default")
      (node (ref "BTN") (pin "4") (pinfunction "4_4") (pintype "passive"))
    )
    (net (code "61") (name "unconnected-(RESET-Pad2)") (class "Default")
      (node (ref "RESET") (pin "2") (pinfunction "2_2") (pintype "passive"))
    )
    (net (code "62") (name "unconnected-(RESET-Pad3)") (class "Default")
      (node (ref "RESET") (pin "3") (pinfunction "3_3") (pintype "passive"))
    )
    (net (code "63") (name "unconnected-(U1-PadNC)") (class "Default")
      (node (ref "U1") (pin "NC") (pinfunction "NC_NC") (pintype "no_connect"))
    )
    (net (code "64") (name "unconnected-(U1-PadRESERVED_1)") (class "Default")
      (node (ref "U1") (pin "RESERVED_1") (pinfunction "RESERVED_1_RESERVED_1") (pintype "bidirectional"))
    )
    (net (code "65") (name "unconnected-(U1-PadRESERVED_2)") (class "Default")
      (node (ref "U1") (pin "RESERVED_2") (pinfunction "RESERVED_2_RESERVED_2") (pintype "bidirectional"))
    )
    (net (code "66") (name "unconnected-(U1-PadRESERVED_3)") (class "Default")
      (node (ref "U1") (pin "RESERVED_3") (pinfunction "RESERVED_3_RESERVED_3") (pintype "bidirectional"))
    )
    (net (code "67") (name "unconnected-(U1-PadWL_RS232_RX)") (class "Default")
      (node (ref "U1") (pin "WL_RS232_RX") (pinfunction "WL_RS232_RX_WL_RS232_RX") (pintype "input"))
    )
    (net (code "68") (name "unconnected-(U1-PadWL_RS232_TX)") (class "Default")
      (node (ref "U1") (pin "WL_RS232_TX") (pinfunction "WL_RS232_TX_WL_RS232_TX") (pintype "output"))
    )
    (net (code "69") (name "unconnected-(U2F-PC13-Pad2)") (class "Default")
      (node (ref "U2") (pin "2") (pinfunction "PC13_2") (pintype "bidirectional"))
    )
  )
)
